# etl1.net
KiCad netlist of a schematic drawn in EAGLE
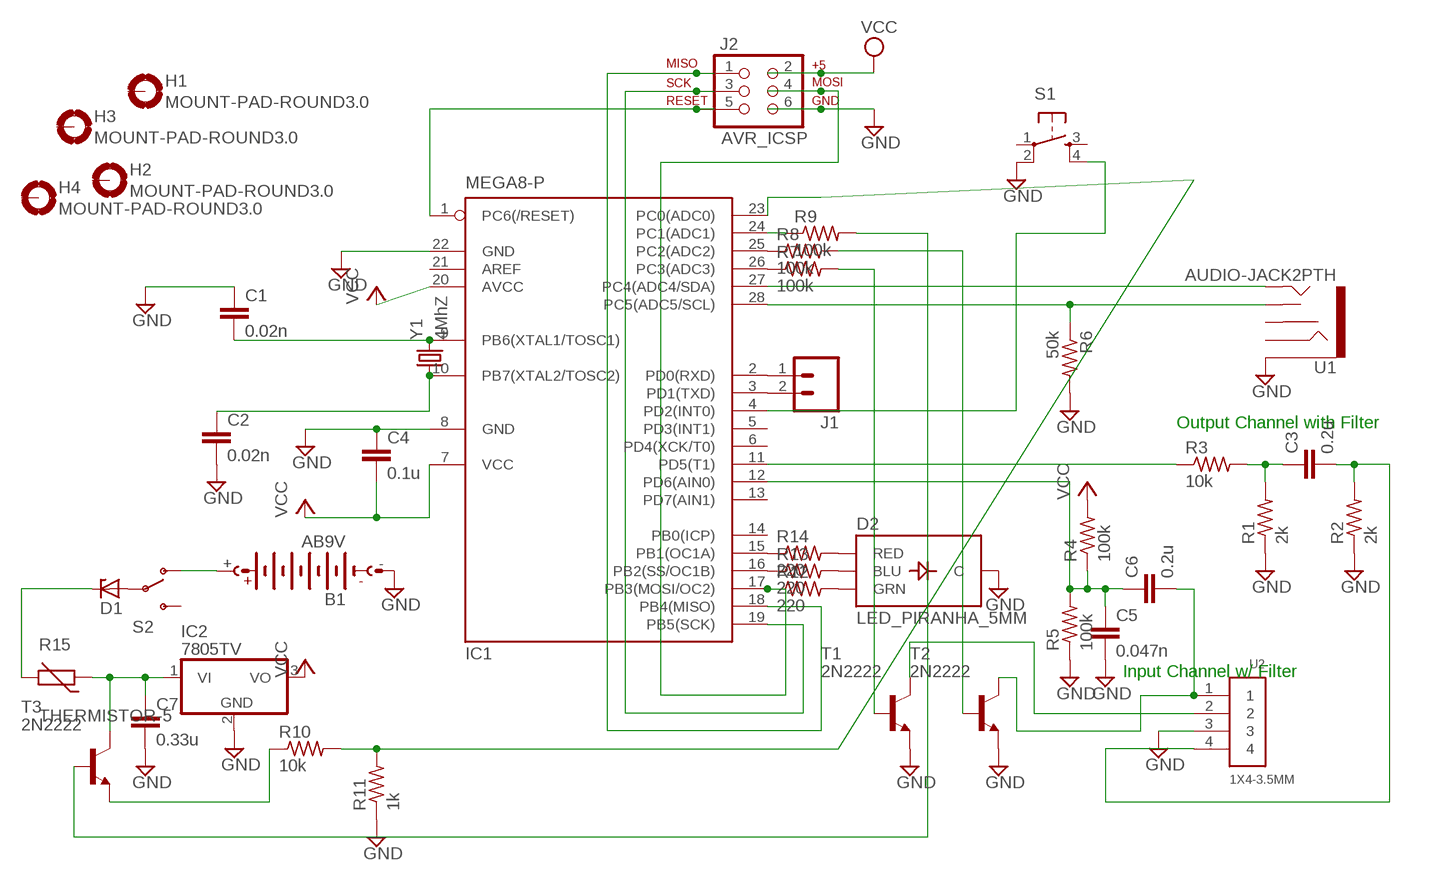
[diagram p0: schematic, sheet 1]

(export (version "E")
  (design (tool "Eeschema 10.0.6"))
  (components
    (comp (ref "B1")
      (value "AB9V")
      (footprint "eagle-import:AB9V")
      (libsource (lib "eagle-import") (part "AB9V"))
    )
    (comp (ref "C1")
      (value "0.02n")
      (footprint "eagle-import:C5B3")
      (libsource (lib "eagle-import") (part "C5/3"))
    )
    (comp (ref "C2")
      (value "0.02n")
      (footprint "eagle-import:C5B3")
      (libsource (lib "eagle-import") (part "C5/3"))
    )
    (comp (ref "C3")
      (value "0.2u")
      (footprint "eagle-import:C5B3")
      (libsource (lib "eagle-import") (part "C5/3"))
    )
    (comp (ref "C4")
      (value "0.1u")
      (footprint "eagle-import:C5B3")
      (libsource (lib "eagle-import") (part "C5/3"))
    )
    (comp (ref "C5")
      (value "0.047n")
      (footprint "eagle-import:C5B3")
      (libsource (lib "eagle-import") (part "C5/3"))
    )
    (comp (ref "C6")
      (value "0.2u")
      (footprint "eagle-import:C5B3")
      (libsource (lib "eagle-import") (part "C5/3"))
    )
    (comp (ref "C7")
      (value "0.33u")
      (footprint "eagle-import:C5B3")
      (libsource (lib "eagle-import") (part "C5/3"))
    )
    (comp (ref "D1")
      (value "ZENER-DIODEZD-10")
      (footprint "eagle-import:ZDIO-10")
      (libsource (lib "eagle-import") (part "ZENER-DIODEZD-10"))
    )
    (comp (ref "D2")
      (value "LED_PIRANHA_5MM")
      (footprint "eagle-import:LED_PIRANHA_5MM")
      (libsource (lib "eagle-import") (part "LED_PIRANHA_5MM"))
    )
    (comp (ref "H1")
      (value "MOUNT-PAD-ROUND3.0")
      (footprint "eagle-import:3,0-PAD")
      (libsource (lib "eagle-import") (part "MOUNT-PAD-ROUND3.0"))
    )
    (comp (ref "H2")
      (value "MOUNT-PAD-ROUND3.0")
      (footprint "eagle-import:3,0-PAD")
      (libsource (lib "eagle-import") (part "MOUNT-PAD-ROUND3.0"))
    )
    (comp (ref "H3")
      (value "MOUNT-PAD-ROUND3.0")
      (footprint "eagle-import:3,0-PAD")
      (libsource (lib "eagle-import") (part "MOUNT-PAD-ROUND3.0"))
    )
    (comp (ref "H4")
      (value "MOUNT-PAD-ROUND3.0")
      (footprint "eagle-import:3,0-PAD")
      (libsource (lib "eagle-import") (part "MOUNT-PAD-ROUND3.0"))
    )
    (comp (ref "IC1")
      (value "MEGA8-P")
      (footprint "eagle-import:DIL28-3")
      (libsource (lib "eagle-import") (part "MEGA8-P"))
    )
    (comp (ref "IC2")
      (value "7805TV")
      (footprint "eagle-import:TO220V")
      (libsource (lib "eagle-import") (part "78TV05"))
    )
    (comp (ref "J1")
      (value "M02LOCK")
      (footprint "eagle-import:1X02_LOCK")
      (libsource (lib "eagle-import") (part "M02LOCK"))
    )
    (comp (ref "J2")
      (value "AVR_ICSP")
      (footprint "eagle-import:2X3-NS")
      (libsource (lib "eagle-import") (part "AVR_SPI_PRG_6NS"))
    )
    (comp (ref "R1")
      (value "2k")
      (footprint "eagle-import:0207_10")
      (libsource (lib "eagle-import") (part "R-US_0207/10"))
    )
    (comp (ref "R2")
      (value "2k")
      (footprint "eagle-import:0207_10")
      (libsource (lib "eagle-import") (part "R-US_0207/10"))
    )
    (comp (ref "R3")
      (value "10k")
      (footprint "eagle-import:0207_10")
      (libsource (lib "eagle-import") (part "R-US_0207/10"))
    )
    (comp (ref "R4")
      (value "100k")
      (footprint "eagle-import:0207_10")
      (libsource (lib "eagle-import") (part "R-US_0207/10"))
    )
    (comp (ref "R5")
      (value "100k")
      (footprint "eagle-import:0207_10")
      (libsource (lib "eagle-import") (part "R-US_0207/10"))
    )
    (comp (ref "R6")
      (value "50k")
      (footprint "eagle-import:0207_10")
      (libsource (lib "eagle-import") (part "R-US_0207/10"))
    )
    (comp (ref "R7")
      (value "100k")
      (footprint "eagle-import:0207_10")
      (libsource (lib "eagle-import") (part "R-US_0207/10"))
    )
    (comp (ref "R8")
      (value "100k")
      (footprint "eagle-import:0207_10")
      (libsource (lib "eagle-import") (part "R-US_0207/10"))
    )
    (comp (ref "R9")
      (value "100k")
      (footprint "eagle-import:0207_10")
      (libsource (lib "eagle-import") (part "R-US_0207/10"))
    )
    (comp (ref "R10")
      (value "10k")
      (footprint "eagle-import:0207_10")
      (libsource (lib "eagle-import") (part "R-US_0207/10"))
    )
    (comp (ref "R11")
      (value "1k")
      (footprint "eagle-import:0207_10")
      (libsource (lib "eagle-import") (part "R-US_0207/10"))
    )
    (comp (ref "R12")
      (value "220")
      (footprint "eagle-import:0207_10")
      (libsource (lib "eagle-import") (part "R-US_0207/10"))
    )
    (comp (ref "R13")
      (value "220")
      (footprint "eagle-import:0207_10")
      (libsource (lib "eagle-import") (part "R-US_0207/10"))
    )
    (comp (ref "R14")
      (value "220")
      (footprint "eagle-import:0207_10")
      (libsource (lib "eagle-import") (part "R-US_0207/10"))
    )
    (comp (ref "R15")
      (value "THERMISTOR-5")
      (footprint "eagle-import:R-5")
      (libsource (lib "eagle-import") (part "THERMISTOR-5"))
    )
    (comp (ref "S1")
      (value "TAC_SWITCHPTH")
      (footprint "eagle-import:TACTILE-PTH")
      (libsource (lib "eagle-import") (part "TAC_SWITCHPTH"))
    )
    (comp (ref "S2")
      (value "SWITCH-SPDTPTH")
      (footprint "eagle-import:SWITCH-SPDT")
      (libsource (lib "eagle-import") (part "SWITCH-SPDTPTH"))
    )
    (comp (ref "T1")
      (value "2N2222")
      (footprint "eagle-import:TO92-EBC-OVAL")
      (libsource (lib "eagle-import") (part "2N2222"))
    )
    (comp (ref "T2")
      (value "2N2222")
      (footprint "eagle-import:TO92-EBC-OVAL")
      (libsource (lib "eagle-import") (part "2N2222"))
    )
    (comp (ref "T3")
      (value "2N2222")
      (footprint "eagle-import:TO92-EBC-OVAL")
      (libsource (lib "eagle-import") (part "2N2222"))
    )
    (comp (ref "U1")
      (value "AUDIO-JACK2PTH")
      (footprint "eagle-import:AUDIO-JACK")
      (libsource (lib "eagle-import") (part "AUDIO-JACK2PTH"))
    )
    (comp (ref "U2")
      (value "1X4-3.5MM")
      (footprint "eagle-import:1X04-3.5MM")
      (libsource (lib "eagle-import") (part "1X4-3.5MM"))
    )
    (comp (ref "Y1")
      (value "4MhZ")
      (footprint "eagle-import:HC49US")
      (libsource (lib "eagle-import") (part "CRYSTALHC49US"))
    )
  )
  (nets
    (net (code "1") (name "GND") (class "Default")
      (node (ref "B1") (pin "-") (pinfunction "-_-") (pintype "passive"))
      (node (ref "C1") (pin "1") (pinfunction "1_1") (pintype "passive"))
      (node (ref "C2") (pin "2") (pinfunction "2_2") (pintype "passive"))
      (node (ref "C4") (pin "1") (pinfunction "1_1") (pintype "passive"))
      (node (ref "C5") (pin "2") (pinfunction "2_2") (pintype "passive"))
      (node (ref "C7") (pin "2") (pinfunction "2_2") (pintype "passive"))
      (node (ref "D2") (pin "-") (pinfunction "C_-") (pintype "bidirectional"))
      (node (ref "IC1") (pin "22") (pinfunction "GND_22") (pintype "power_in"))
      (node (ref "IC1") (pin "8") (pinfunction "GND_8") (pintype "power_in"))
      (node (ref "IC2") (pin "2") (pinfunction "GND_2") (pintype "passive"))
      (node (ref "J2") (pin "6") (pinfunction "6_6") (pintype "passive"))
      (node (ref "R1") (pin "1") (pinfunction "1_1") (pintype "passive"))
      (node (ref "R11") (pin "1") (pinfunction "1_1") (pintype "passive"))
      (node (ref "R2") (pin "1") (pinfunction "1_1") (pintype "passive"))
      (node (ref "R5") (pin "1") (pinfunction "1_1") (pintype "passive"))
      (node (ref "R6") (pin "2") (pinfunction "2_2") (pintype "passive"))
      (node (ref "S1") (pin "2") (pinfunction "2_2") (pintype "passive"))
      (node (ref "T1") (pin "E") (pinfunction "E_E") (pintype "passive"))
      (node (ref "T2") (pin "E") (pinfunction "E_E") (pintype "passive"))
      (node (ref "U1") (pin "SLEEVE") (pinfunction "SLEEVE_SLEEVE") (pintype "bidirectional"))
      (node (ref "U2") (pin "3") (pinfunction "3_3") (pintype "bidirectional"))
    )
    (net (code "2") (name "Net-(C3-Pad1)") (class "Default")
      (node (ref "C3") (pin "1") (pinfunction "1_1") (pintype "passive"))
      (node (ref "R1") (pin "2") (pinfunction "2_2") (pintype "passive"))
      (node (ref "R3") (pin "2") (pinfunction "2_2") (pintype "passive"))
    )
    (net (code "3") (name "Net-(C3-Pad2)") (class "Default")
      (node (ref "C3") (pin "2") (pinfunction "2_2") (pintype "passive"))
      (node (ref "R2") (pin "2") (pinfunction "2_2") (pintype "passive"))
      (node (ref "U2") (pin "4") (pinfunction "4_4") (pintype "bidirectional"))
    )
    (net (code "4") (name "Net-(C6-Pad2)") (class "Default")
      (node (ref "C6") (pin "2") (pinfunction "2_2") (pintype "passive"))
      (node (ref "T2") (pin "C") (pinfunction "C_C") (pintype "passive"))
      (node (ref "U2") (pin "1") (pinfunction "1_1") (pintype "bidirectional"))
    )
    (net (code "5") (name "Net-(D1-PadC)") (class "Default")
      (node (ref "D1") (pin "C") (pinfunction "C_C") (pintype "passive"))
      (node (ref "R15") (pin "2") (pinfunction "2_2") (pintype "passive"))
    )
    (net (code "6") (name "Net-(D2-BLU)") (class "Default")
      (node (ref "D2") (pin "B") (pinfunction "BLU_B") (pintype "bidirectional"))
      (node (ref "R13") (pin "2") (pinfunction "2_2") (pintype "passive"))
    )
    (net (code "7") (name "Net-(D2-GRN)") (class "Default")
      (node (ref "D2") (pin "G") (pinfunction "GRN_G") (pintype "bidirectional"))
      (node (ref "R12") (pin "2") (pinfunction "2_2") (pintype "passive"))
    )
    (net (code "8") (name "Net-(D2-RED)") (class "Default")
      (node (ref "D2") (pin "R") (pinfunction "RED_R") (pintype "bidirectional"))
      (node (ref "R14") (pin "2") (pinfunction "2_2") (pintype "passive"))
    )
    (net (code "9") (name "Net-(IC1-PB1(OC1A))") (class "Default")
      (node (ref "IC1") (pin "15") (pinfunction "PB1(OC1A)_15") (pintype "bidirectional"))
      (node (ref "R14") (pin "1") (pinfunction "1_1") (pintype "passive"))
    )
    (net (code "10") (name "Net-(IC1-PB2(SS{slash}OC1B))") (class "Default")
      (node (ref "IC1") (pin "16") (pinfunction "PB2(SS/OC1B)_16") (pintype "bidirectional"))
      (node (ref "R13") (pin "1") (pinfunction "1_1") (pintype "passive"))
    )
    (net (code "11") (name "Net-(IC1-PB3(MOSI{slash}OC2))") (class "Default")
      (node (ref "IC1") (pin "17") (pinfunction "PB3(MOSI/OC2)_17") (pintype "bidirectional"))
      (node (ref "J2") (pin "4") (pinfunction "4_4") (pintype "passive"))
      (node (ref "R12") (pin "1") (pinfunction "1_1") (pintype "passive"))
    )
    (net (code "12") (name "Net-(IC1-PB4(MISO))") (class "Default")
      (node (ref "IC1") (pin "18") (pinfunction "PB4(MISO)_18") (pintype "bidirectional"))
      (node (ref "J2") (pin "1") (pinfunction "1_1") (pintype "passive"))
    )
    (net (code "13") (name "Net-(IC1-PB5(SCK))") (class "Default")
      (node (ref "IC1") (pin "19") (pinfunction "PB5(SCK)_19") (pintype "bidirectional"))
      (node (ref "J2") (pin "3") (pinfunction "3_3") (pintype "passive"))
    )
    (net (code "14") (name "Net-(IC1-PB6(XTAL1{slash}TOSC1))") (class "Default")
      (node (ref "C1") (pin "2") (pinfunction "2_2") (pintype "passive"))
      (node (ref "IC1") (pin "9") (pinfunction "PB6(XTAL1/TOSC1)_9") (pintype "bidirectional"))
      (node (ref "Y1") (pin "2") (pinfunction "2_2") (pintype "passive"))
    )
    (net (code "15") (name "Net-(IC1-PB7(XTAL2{slash}TOSC2))") (class "Default")
      (node (ref "C2") (pin "1") (pinfunction "1_1") (pintype "passive"))
      (node (ref "IC1") (pin "10") (pinfunction "PB7(XTAL2/TOSC2)_10") (pintype "bidirectional"))
      (node (ref "Y1") (pin "1") (pinfunction "1_1") (pintype "passive"))
    )
    (net (code "16") (name "Net-(IC1-PC0(ADC0))") (class "Default")
      (node (ref "IC1") (pin "23") (pinfunction "PC0(ADC0)_23") (pintype "bidirectional"))
      (node (ref "R10") (pin "2") (pinfunction "2_2") (pintype "passive"))
      (node (ref "R11") (pin "2") (pinfunction "2_2") (pintype "passive"))
    )
    (net (code "17") (name "Net-(IC1-PC1(ADC1))") (class "Default")
      (node (ref "IC1") (pin "24") (pinfunction "PC1(ADC1)_24") (pintype "bidirectional"))
      (node (ref "R9") (pin "1") (pinfunction "1_1") (pintype "passive"))
    )
    (net (code "18") (name "Net-(IC1-PC2(ADC2))") (class "Default")
      (node (ref "IC1") (pin "25") (pinfunction "PC2(ADC2)_25") (pintype "bidirectional"))
      (node (ref "R8") (pin "1") (pinfunction "1_1") (pintype "passive"))
    )
    (net (code "19") (name "Net-(IC1-PC3(ADC3))") (class "Default")
      (node (ref "IC1") (pin "26") (pinfunction "PC3(ADC3)_26") (pintype "bidirectional"))
      (node (ref "R7") (pin "1") (pinfunction "1_1") (pintype "passive"))
    )
    (net (code "20") (name "Net-(IC1-PC4(ADC4{slash}SDA))") (class "Default")
      (node (ref "IC1") (pin "27") (pinfunction "PC4(ADC4/SDA)_27") (pintype "bidirectional"))
      (node (ref "U1") (pin "TIP") (pinfunction "TIP_TIP") (pintype "bidirectional"))
    )
    (net (code "21") (name "Net-(IC1-PC5(ADC5{slash}SCL))") (class "Default")
      (node (ref "IC1") (pin "28") (pinfunction "PC5(ADC5/SCL)_28") (pintype "bidirectional"))
      (node (ref "R6") (pin "1") (pinfunction "1_1") (pintype "passive"))
      (node (ref "U1") (pin "TSH") (pinfunction "TSH_TSH") (pintype "bidirectional"))
    )
    (net (code "22") (name "Net-(IC1-PC6({slash}RESET))") (class "Default")
      (node (ref "IC1") (pin "1") (pinfunction "PC6(/RESET)_1") (pintype "bidirectional"))
      (node (ref "J2") (pin "5") (pinfunction "5_5") (pintype "passive"))
    )
    (net (code "23") (name "Net-(IC1-PD0(RXD))") (class "Default")
      (node (ref "IC1") (pin "2") (pinfunction "PD0(RXD)_2") (pintype "bidirectional"))
      (node (ref "J1") (pin "1") (pinfunction "1_1") (pintype "passive"))
    )
    (net (code "24") (name "Net-(IC1-PD1(TXD))") (class "Default")
      (node (ref "IC1") (pin "3") (pinfunction "PD1(TXD)_3") (pintype "bidirectional"))
      (node (ref "J1") (pin "2") (pinfunction "2_2") (pintype "passive"))
    )
    (net (code "25") (name "Net-(IC1-PD2(INT0))") (class "Default")
      (node (ref "IC1") (pin "4") (pinfunction "PD2(INT0)_4") (pintype "bidirectional"))
      (node (ref "S1") (pin "4") (pinfunction "4_4") (pintype "passive"))
    )
    (net (code "26") (name "Net-(IC1-PD5(T1))") (class "Default")
      (node (ref "IC1") (pin "11") (pinfunction "PD5(T1)_11") (pintype "bidirectional"))
      (node (ref "R3") (pin "1") (pinfunction "1_1") (pintype "passive"))
    )
    (net (code "27") (name "Net-(IC1-PD6(AIN0))") (class "Default")
      (node (ref "C5") (pin "1") (pinfunction "1_1") (pintype "passive"))
      (node (ref "C6") (pin "1") (pinfunction "1_1") (pintype "passive"))
      (node (ref "IC1") (pin "12") (pinfunction "PD6(AIN0)_12") (pintype "bidirectional"))
      (node (ref "R4") (pin "1") (pinfunction "1_1") (pintype "passive"))
      (node (ref "R5") (pin "2") (pinfunction "2_2") (pintype "passive"))
    )
    (net (code "28") (name "Net-(IC2-VI)") (class "Default")
      (node (ref "C7") (pin "1") (pinfunction "1_1") (pintype "passive"))
      (node (ref "IC2") (pin "1") (pinfunction "VI_1") (pintype "input"))
      (node (ref "R15") (pin "1") (pinfunction "1_1") (pintype "passive"))
      (node (ref "T3") (pin "C") (pinfunction "C_C") (pintype "passive"))
    )
    (net (code "29") (name "Net-(R7-Pad2)") (class "Default")
      (node (ref "R7") (pin "2") (pinfunction "2_2") (pintype "passive"))
      (node (ref "T1") (pin "B") (pinfunction "B_B") (pintype "passive"))
    )
    (net (code "30") (name "Net-(R8-Pad2)") (class "Default")
      (node (ref "R8") (pin "2") (pinfunction "2_2") (pintype "passive"))
      (node (ref "T2") (pin "B") (pinfunction "B_B") (pintype "passive"))
    )
    (net (code "31") (name "Net-(R9-Pad2)") (class "Default")
      (node (ref "R9") (pin "2") (pinfunction "2_2") (pintype "passive"))
      (node (ref "T3") (pin "B") (pinfunction "B_B") (pintype "passive"))
    )
    (net (code "32") (name "Net-(R10-Pad1)") (class "Default")
      (node (ref "R10") (pin "1") (pinfunction "1_1") (pintype "passive"))
      (node (ref "T3") (pin "E") (pinfunction "E_E") (pintype "passive"))
    )
    (net (code "33") (name "Net-(S2-O)") (class "Default")
      (node (ref "B1") (pin "+") (pinfunction "+_+") (pintype "passive"))
      (node (ref "S2") (pin "1") (pinfunction "O_1") (pintype "passive"))
    )
    (net (code "34") (name "Net-(S2-P)") (class "Default")
      (node (ref "D1") (pin "A") (pinfunction "A_A") (pintype "passive"))
      (node (ref "S2") (pin "2") (pinfunction "P_2") (pintype "passive"))
    )
    (net (code "35") (name "Net-(T1-PadC)") (class "Default")
      (node (ref "T1") (pin "C") (pinfunction "C_C") (pintype "passive"))
      (node (ref "U2") (pin "2") (pinfunction "2_2") (pintype "bidirectional"))
    )
    (net (code "36") (name "VCC") (class "Default")
      (node (ref "C4") (pin "2") (pinfunction "2_2") (pintype "passive"))
      (node (ref "IC1") (pin "20") (pinfunction "AVCC_20") (pintype "power_in"))
      (node (ref "IC1") (pin "7") (pinfunction "VCC_7") (pintype "power_in"))
      (node (ref "IC2") (pin "3") (pinfunction "VO_3") (pintype "passive"))
      (node (ref "J2") (pin "2") (pinfunction "2_2") (pintype "passive"))
      (node (ref "R4") (pin "2") (pinfunction "2_2") (pintype "passive"))
    )
    (net (code "37") (name "unconnected-(H1-MOUNT-PadB3,0)") (class "Default")
      (node (ref "H1") (pin "B3,0") (pinfunction "MOUNT_B3,0") (pintype "passive"))
    )
    (net (code "38") (name "unconnected-(H2-MOUNT-PadB3,0)") (class "Default")
      (node (ref "H2") (pin "B3,0") (pinfunction "MOUNT_B3,0") (pintype "passive"))
    )
    (net (code "39") (name "unconnected-(H3-MOUNT-PadB3,0)") (class "Default")
      (node (ref "H3") (pin "B3,0") (pinfunction "MOUNT_B3,0") (pintype "passive"))
    )
    (net (code "40") (name "unconnected-(H4-MOUNT-PadB3,0)") (class "Default")
      (node (ref "H4") (pin "B3,0") (pinfunction "MOUNT_B3,0") (pintype "passive"))
    )
    (net (code "41") (name "unconnected-(IC1-AREF-Pad21)") (class "Default")
      (node (ref "IC1") (pin "21") (pinfunction "AREF_21") (pintype "passive"))
    )
    (net (code "42") (name "unconnected-(IC1-PB0(ICP)-Pad14)") (class "Default")
      (node (ref "IC1") (pin "14") (pinfunction "PB0(ICP)_14") (pintype "bidirectional"))
    )
    (net (code "43") (name "unconnected-(IC1-PD3(INT1)-Pad5)") (class "Default")
      (node (ref "IC1") (pin "5") (pinfunction "PD3(INT1)_5") (pintype "bidirectional"))
    )
    (net (code "44") (name "unconnected-(IC1-PD4(XCK{slash}T0)-Pad6)") (class "Default")
      (node (ref "IC1") (pin "6") (pinfunction "PD4(XCK/T0)_6") (pintype "bidirectional"))
    )
    (net (code "45") (name "unconnected-(IC1-PD7(AIN1)-Pad13)") (class "Default")
      (node (ref "IC1") (pin "13") (pinfunction "PD7(AIN1)_13") (pintype "bidirectional"))
    )
    (net (code "46") (name "unconnected-(S1-Pad1)") (class "Default")
      (node (ref "S1") (pin "1") (pinfunction "1_1") (pintype "passive"))
    )
    (net (code "47") (name "unconnected-(S1-Pad3)") (class "Default")
      (node (ref "S1") (pin "3") (pinfunction "3_3") (pintype "passive"))
    )
    (net (code "48") (name "unconnected-(S2-S-Pad3)") (class "Default")
      (node (ref "S2") (pin "3") (pinfunction "S_3") (pintype "passive"))
    )
    (net (code "49") (name "unconnected-(U1-PadRING)") (class "Default")
      (node (ref "U1") (pin "RING") (pinfunction "RING_RING") (pintype "bidirectional"))
    )
    (net (code "50") (name "unconnected-(U1-PadRSH)") (class "Default")
      (node (ref "U1") (pin "RSH") (pinfunction "RSH_RSH") (pintype "bidirectional"))
    )
  )
)
